# scb_connectors.net
KiCad netlist of a schematic drawn in Altium Designer
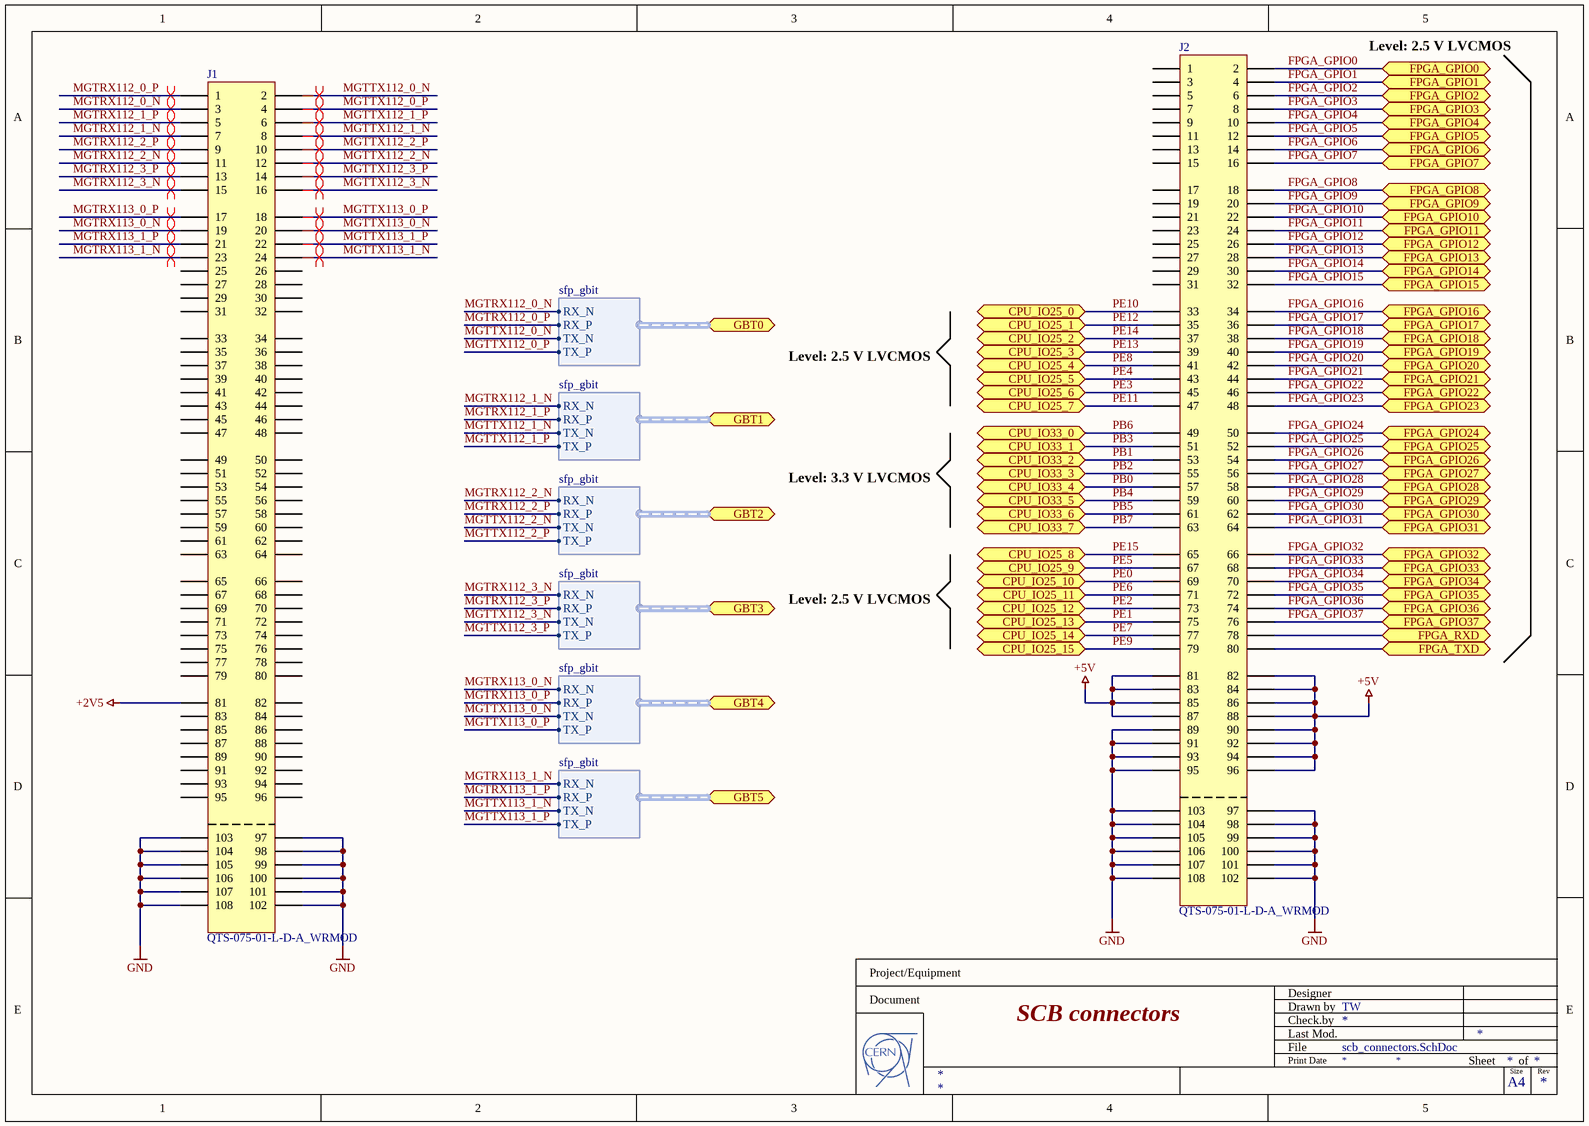
[diagram p0: scb_connectors.SchDoc]

(export (version "E")
  (design (tool "Eeschema 10.0.6"))
  (components
    (comp (ref "J1")
      (value "QTS-075-01-L-D-A_WRMOD")
      (footprint "QTS-075-01-L-D-A_WRMOD")
      (description "High Speed Ground Plane Header")
      (libsource (lib "wr_switch") (part "QTS-075-01-L-D-A_WRMOD"))
    )
    (comp (ref "J2")
      (value "QTS-075-01-L-D-A_WRMOD")
      (footprint "QTS-075-01-L-D-A_WRMOD")
      (description "High Speed Ground Plane Header")
      (libsource (lib "wr_switch") (part "QTS-075-01-L-D-A_WRMOD"))
    )
  )
  (nets
    (net (code "2") (name "+2V5") (class "Default")
      (node (ref "J1") (pin "81") (pinfunction "81_81") (pintype "passive"))
    )
    (net (code "3") (name "+5V") (class "Default")
      (node (ref "J2") (pin "81") (pinfunction "81_81") (pintype "passive"))
      (node (ref "J2") (pin "82") (pinfunction "82_82") (pintype "passive"))
      (node (ref "J2") (pin "83") (pinfunction "83_83") (pintype "passive"))
      (node (ref "J2") (pin "84") (pinfunction "84_84") (pintype "passive"))
      (node (ref "J2") (pin "85") (pinfunction "85_85") (pintype "passive"))
      (node (ref "J2") (pin "86") (pinfunction "86_86") (pintype "passive"))
      (node (ref "J2") (pin "87") (pinfunction "87_87") (pintype "passive"))
      (node (ref "J2") (pin "88") (pinfunction "88_88") (pintype "passive"))
      (node (ref "J2") (pin "90") (pinfunction "90_90") (pintype "passive"))
      (node (ref "J2") (pin "92") (pinfunction "92_92") (pintype "passive"))
      (node (ref "J2") (pin "94") (pinfunction "94_94") (pintype "passive"))
      (node (ref "J2") (pin "96") (pinfunction "96_96") (pintype "passive"))
    )
    (net (code "4") (name "/FPGA_GPIO0") (class "Default")
      (node (ref "J2") (pin "2") (pinfunction "2_2") (pintype "passive"))
    )
    (net (code "5") (name "/FPGA_GPIO1") (class "Default")
      (node (ref "J2") (pin "4") (pinfunction "4_4") (pintype "passive"))
    )
    (net (code "6") (name "/FPGA_GPIO2") (class "Default")
      (node (ref "J2") (pin "6") (pinfunction "6_6") (pintype "passive"))
    )
    (net (code "7") (name "/FPGA_GPIO3") (class "Default")
      (node (ref "J2") (pin "8") (pinfunction "8_8") (pintype "passive"))
    )
    (net (code "8") (name "/FPGA_GPIO4") (class "Default")
      (node (ref "J2") (pin "10") (pinfunction "10_10") (pintype "passive"))
    )
    (net (code "9") (name "/FPGA_GPIO5") (class "Default")
      (node (ref "J2") (pin "12") (pinfunction "12_12") (pintype "passive"))
    )
    (net (code "10") (name "/FPGA_GPIO6") (class "Default")
      (node (ref "J2") (pin "14") (pinfunction "14_14") (pintype "passive"))
    )
    (net (code "11") (name "/FPGA_GPIO7") (class "Default")
      (node (ref "J2") (pin "16") (pinfunction "16_16") (pintype "passive"))
    )
    (net (code "12") (name "/FPGA_GPIO8") (class "Default")
      (node (ref "J2") (pin "18") (pinfunction "18_18") (pintype "passive"))
    )
    (net (code "13") (name "/FPGA_GPIO9") (class "Default")
      (node (ref "J2") (pin "20") (pinfunction "20_20") (pintype "passive"))
    )
    (net (code "14") (name "/FPGA_GPIO10") (class "Default")
      (node (ref "J2") (pin "22") (pinfunction "22_22") (pintype "passive"))
    )
    (net (code "15") (name "/FPGA_GPIO11") (class "Default")
      (node (ref "J2") (pin "24") (pinfunction "24_24") (pintype "passive"))
    )
    (net (code "16") (name "/FPGA_GPIO12") (class "Default")
      (node (ref "J2") (pin "26") (pinfunction "26_26") (pintype "passive"))
    )
    (net (code "17") (name "/FPGA_GPIO13") (class "Default")
      (node (ref "J2") (pin "28") (pinfunction "28_28") (pintype "passive"))
    )
    (net (code "18") (name "/FPGA_GPIO14") (class "Default")
      (node (ref "J2") (pin "30") (pinfunction "30_30") (pintype "passive"))
    )
    (net (code "19") (name "/FPGA_GPIO15") (class "Default")
      (node (ref "J2") (pin "32") (pinfunction "32_32") (pintype "passive"))
    )
    (net (code "20") (name "/FPGA_GPIO16") (class "Default")
      (node (ref "J2") (pin "34") (pinfunction "34_34") (pintype "passive"))
    )
    (net (code "21") (name "/FPGA_GPIO17") (class "Default")
      (node (ref "J2") (pin "36") (pinfunction "36_36") (pintype "passive"))
    )
    (net (code "22") (name "/FPGA_GPIO18") (class "Default")
      (node (ref "J2") (pin "38") (pinfunction "38_38") (pintype "passive"))
    )
    (net (code "23") (name "/FPGA_GPIO19") (class "Default")
      (node (ref "J2") (pin "40") (pinfunction "40_40") (pintype "passive"))
    )
    (net (code "24") (name "/FPGA_GPIO20") (class "Default")
      (node (ref "J2") (pin "42") (pinfunction "42_42") (pintype "passive"))
    )
    (net (code "25") (name "/FPGA_GPIO21") (class "Default")
      (node (ref "J2") (pin "44") (pinfunction "44_44") (pintype "passive"))
    )
    (net (code "26") (name "/FPGA_GPIO22") (class "Default")
      (node (ref "J2") (pin "46") (pinfunction "46_46") (pintype "passive"))
    )
    (net (code "27") (name "/FPGA_GPIO23") (class "Default")
      (node (ref "J2") (pin "48") (pinfunction "48_48") (pintype "passive"))
    )
    (net (code "28") (name "/FPGA_GPIO24") (class "Default")
      (node (ref "J2") (pin "50") (pinfunction "50_50") (pintype "passive"))
    )
    (net (code "29") (name "/FPGA_GPIO25") (class "Default")
      (node (ref "J2") (pin "52") (pinfunction "52_52") (pintype "passive"))
    )
    (net (code "30") (name "/FPGA_GPIO26") (class "Default")
      (node (ref "J2") (pin "54") (pinfunction "54_54") (pintype "passive"))
    )
    (net (code "31") (name "/FPGA_GPIO27") (class "Default")
      (node (ref "J2") (pin "56") (pinfunction "56_56") (pintype "passive"))
    )
    (net (code "32") (name "/FPGA_GPIO28") (class "Default")
      (node (ref "J2") (pin "58") (pinfunction "58_58") (pintype "passive"))
    )
    (net (code "33") (name "/FPGA_GPIO29") (class "Default")
      (node (ref "J2") (pin "60") (pinfunction "60_60") (pintype "passive"))
    )
    (net (code "34") (name "/FPGA_GPIO30") (class "Default")
      (node (ref "J2") (pin "62") (pinfunction "62_62") (pintype "passive"))
    )
    (net (code "35") (name "/FPGA_GPIO31") (class "Default")
      (node (ref "J2") (pin "64") (pinfunction "64_64") (pintype "passive"))
    )
    (net (code "36") (name "/FPGA_GPIO32") (class "Default")
      (node (ref "J2") (pin "66") (pinfunction "66_66") (pintype "passive"))
    )
    (net (code "37") (name "/FPGA_GPIO33") (class "Default")
      (node (ref "J2") (pin "68") (pinfunction "68_68") (pintype "passive"))
    )
    (net (code "38") (name "/FPGA_GPIO34") (class "Default")
      (node (ref "J2") (pin "70") (pinfunction "70_70") (pintype "passive"))
    )
    (net (code "39") (name "/FPGA_GPIO35") (class "Default")
      (node (ref "J2") (pin "72") (pinfunction "72_72") (pintype "passive"))
    )
    (net (code "40") (name "/FPGA_GPIO36") (class "Default")
      (node (ref "J2") (pin "74") (pinfunction "74_74") (pintype "passive"))
    )
    (net (code "41") (name "/FPGA_GPIO37") (class "Default")
      (node (ref "J2") (pin "76") (pinfunction "76_76") (pintype "passive"))
    )
    (net (code "42") (name "/FPGA_RXD") (class "Default")
      (node (ref "J2") (pin "78") (pinfunction "78_78") (pintype "passive"))
    )
    (net (code "43") (name "/FPGA_TXD") (class "Default")
      (node (ref "J2") (pin "80") (pinfunction "80_80") (pintype "passive"))
    )
    (net (code "44") (name "/MGTRX112_0_N") (class "Default")
      (node (ref "J1") (pin "3") (pinfunction "3_3") (pintype "passive"))
    )
    (net (code "45") (name "/MGTRX112_0_P") (class "Default")
      (node (ref "J1") (pin "1") (pinfunction "1_1") (pintype "passive"))
    )
    (net (code "46") (name "/MGTRX112_1_N") (class "Default")
      (node (ref "J1") (pin "7") (pinfunction "7_7") (pintype "passive"))
    )
    (net (code "47") (name "/MGTRX112_1_P") (class "Default")
      (node (ref "J1") (pin "5") (pinfunction "5_5") (pintype "passive"))
    )
    (net (code "48") (name "/MGTRX112_2_N") (class "Default")
      (node (ref "J1") (pin "11") (pinfunction "11_11") (pintype "passive"))
    )
    (net (code "49") (name "/MGTRX112_2_P") (class "Default")
      (node (ref "J1") (pin "9") (pinfunction "9_9") (pintype "passive"))
    )
    (net (code "50") (name "/MGTRX112_3_N") (class "Default")
      (node (ref "J1") (pin "15") (pinfunction "15_15") (pintype "passive"))
    )
    (net (code "51") (name "/MGTRX112_3_P") (class "Default")
      (node (ref "J1") (pin "13") (pinfunction "13_13") (pintype "passive"))
    )
    (net (code "52") (name "/MGTRX113_0_N") (class "Default")
      (node (ref "J1") (pin "19") (pinfunction "19_19") (pintype "passive"))
    )
    (net (code "53") (name "/MGTRX113_0_P") (class "Default")
      (node (ref "J1") (pin "17") (pinfunction "17_17") (pintype "passive"))
    )
    (net (code "54") (name "/MGTRX113_1_N") (class "Default")
      (node (ref "J1") (pin "23") (pinfunction "23_23") (pintype "passive"))
    )
    (net (code "55") (name "/MGTRX113_1_P") (class "Default")
      (node (ref "J1") (pin "21") (pinfunction "21_21") (pintype "passive"))
    )
    (net (code "56") (name "/MGTTX112_0_N") (class "Default")
      (node (ref "J1") (pin "2") (pinfunction "2_2") (pintype "passive"))
    )
    (net (code "57") (name "/MGTTX112_0_P") (class "Default")
      (node (ref "J1") (pin "4") (pinfunction "4_4") (pintype "passive"))
    )
    (net (code "58") (name "/MGTTX112_1_N") (class "Default")
      (node (ref "J1") (pin "8") (pinfunction "8_8") (pintype "passive"))
    )
    (net (code "59") (name "/MGTTX112_1_P") (class "Default")
      (node (ref "J1") (pin "6") (pinfunction "6_6") (pintype "passive"))
    )
    (net (code "60") (name "/MGTTX112_2_N") (class "Default")
      (node (ref "J1") (pin "12") (pinfunction "12_12") (pintype "passive"))
    )
    (net (code "61") (name "/MGTTX112_2_P") (class "Default")
      (node (ref "J1") (pin "10") (pinfunction "10_10") (pintype "passive"))
    )
    (net (code "62") (name "/MGTTX112_3_N") (class "Default")
      (node (ref "J1") (pin "16") (pinfunction "16_16") (pintype "passive"))
    )
    (net (code "63") (name "/MGTTX112_3_P") (class "Default")
      (node (ref "J1") (pin "14") (pinfunction "14_14") (pintype "passive"))
    )
    (net (code "64") (name "/MGTTX113_0_N") (class "Default")
      (node (ref "J1") (pin "20") (pinfunction "20_20") (pintype "passive"))
    )
    (net (code "65") (name "/MGTTX113_0_P") (class "Default")
      (node (ref "J1") (pin "18") (pinfunction "18_18") (pintype "passive"))
    )
    (net (code "66") (name "/MGTTX113_1_N") (class "Default")
      (node (ref "J1") (pin "24") (pinfunction "24_24") (pintype "passive"))
    )
    (net (code "67") (name "/MGTTX113_1_P") (class "Default")
      (node (ref "J1") (pin "22") (pinfunction "22_22") (pintype "passive"))
    )
    (net (code "68") (name "/PB0") (class "Default")
      (node (ref "J2") (pin "57") (pinfunction "57_57") (pintype "passive"))
    )
    (net (code "69") (name "/PB1") (class "Default")
      (node (ref "J2") (pin "53") (pinfunction "53_53") (pintype "passive"))
    )
    (net (code "70") (name "/PB2") (class "Default")
      (node (ref "J2") (pin "55") (pinfunction "55_55") (pintype "passive"))
    )
    (net (code "71") (name "/PB3") (class "Default")
      (node (ref "J2") (pin "51") (pinfunction "51_51") (pintype "passive"))
    )
    (net (code "72") (name "/PB4") (class "Default")
      (node (ref "J2") (pin "59") (pinfunction "59_59") (pintype "passive"))
    )
    (net (code "73") (name "/PB5") (class "Default")
      (node (ref "J2") (pin "61") (pinfunction "61_61") (pintype "passive"))
    )
    (net (code "74") (name "/PB6") (class "Default")
      (node (ref "J2") (pin "49") (pinfunction "49_49") (pintype "passive"))
    )
    (net (code "75") (name "/PB7") (class "Default")
      (node (ref "J2") (pin "63") (pinfunction "63_63") (pintype "passive"))
    )
    (net (code "76") (name "/PE0") (class "Default")
      (node (ref "J2") (pin "69") (pinfunction "69_69") (pintype "passive"))
    )
    (net (code "77") (name "/PE1") (class "Default")
      (node (ref "J2") (pin "75") (pinfunction "75_75") (pintype "passive"))
    )
    (net (code "78") (name "/PE2") (class "Default")
      (node (ref "J2") (pin "73") (pinfunction "73_73") (pintype "passive"))
    )
    (net (code "79") (name "/PE3") (class "Default")
      (node (ref "J2") (pin "45") (pinfunction "45_45") (pintype "passive"))
    )
    (net (code "80") (name "/PE4") (class "Default")
      (node (ref "J2") (pin "43") (pinfunction "43_43") (pintype "passive"))
    )
    (net (code "81") (name "/PE5") (class "Default")
      (node (ref "J2") (pin "67") (pinfunction "67_67") (pintype "passive"))
    )
    (net (code "82") (name "/PE6") (class "Default")
      (node (ref "J2") (pin "71") (pinfunction "71_71") (pintype "passive"))
    )
    (net (code "83") (name "/PE7") (class "Default")
      (node (ref "J2") (pin "77") (pinfunction "77_77") (pintype "passive"))
    )
    (net (code "84") (name "/PE8") (class "Default")
      (node (ref "J2") (pin "41") (pinfunction "41_41") (pintype "passive"))
    )
    (net (code "85") (name "/PE9") (class "Default")
      (node (ref "J2") (pin "79") (pinfunction "79_79") (pintype "passive"))
    )
    (net (code "86") (name "/PE10") (class "Default")
      (node (ref "J2") (pin "33") (pinfunction "33_33") (pintype "passive"))
    )
    (net (code "87") (name "/PE11") (class "Default")
      (node (ref "J2") (pin "47") (pinfunction "47_47") (pintype "passive"))
    )
    (net (code "88") (name "/PE12") (class "Default")
      (node (ref "J2") (pin "35") (pinfunction "35_35") (pintype "passive"))
    )
    (net (code "89") (name "/PE13") (class "Default")
      (node (ref "J2") (pin "39") (pinfunction "39_39") (pintype "passive"))
    )
    (net (code "90") (name "/PE14") (class "Default")
      (node (ref "J2") (pin "37") (pinfunction "37_37") (pintype "passive"))
    )
    (net (code "91") (name "/PE15") (class "Default")
      (node (ref "J2") (pin "65") (pinfunction "65_65") (pintype "passive"))
    )
    (net (code "93") (name "GND") (class "Default")
      (node (ref "J1") (pin "100") (pinfunction "100_100") (pintype "passive"))
      (node (ref "J1") (pin "101") (pinfunction "101_101") (pintype "passive"))
      (node (ref "J1") (pin "102") (pinfunction "102_102") (pintype "passive"))
      (node (ref "J1") (pin "103") (pinfunction "103_103") (pintype "passive"))
      (node (ref "J1") (pin "104") (pinfunction "104_104") (pintype "passive"))
      (node (ref "J1") (pin "105") (pinfunction "105_105") (pintype "passive"))
      (node (ref "J1") (pin "106") (pinfunction "106_106") (pintype "passive"))
      (node (ref "J1") (pin "107") (pinfunction "107_107") (pintype "passive"))
      (node (ref "J1") (pin "108") (pinfunction "108_108") (pintype "passive"))
      (node (ref "J1") (pin "97") (pinfunction "97_97") (pintype "passive"))
      (node (ref "J1") (pin "98") (pinfunction "98_98") (pintype "passive"))
      (node (ref "J1") (pin "99") (pinfunction "99_99") (pintype "passive"))
      (node (ref "J2") (pin "100") (pinfunction "100_100") (pintype "passive"))
      (node (ref "J2") (pin "101") (pinfunction "101_101") (pintype "passive"))
      (node (ref "J2") (pin "102") (pinfunction "102_102") (pintype "passive"))
      (node (ref "J2") (pin "103") (pinfunction "103_103") (pintype "passive"))
      (node (ref "J2") (pin "104") (pinfunction "104_104") (pintype "passive"))
      (node (ref "J2") (pin "105") (pinfunction "105_105") (pintype "passive"))
      (node (ref "J2") (pin "106") (pinfunction "106_106") (pintype "passive"))
      (node (ref "J2") (pin "107") (pinfunction "107_107") (pintype "passive"))
      (node (ref "J2") (pin "108") (pinfunction "108_108") (pintype "passive"))
      (node (ref "J2") (pin "89") (pinfunction "89_89") (pintype "passive"))
      (node (ref "J2") (pin "91") (pinfunction "91_91") (pintype "passive"))
      (node (ref "J2") (pin "93") (pinfunction "93_93") (pintype "passive"))
      (node (ref "J2") (pin "95") (pinfunction "95_95") (pintype "passive"))
      (node (ref "J2") (pin "97") (pinfunction "97_97") (pintype "passive"))
      (node (ref "J2") (pin "98") (pinfunction "98_98") (pintype "passive"))
      (node (ref "J2") (pin "99") (pinfunction "99_99") (pintype "passive"))
    )
    (net (code "94") (name "unconnected-(J1-Pad25)") (class "Default")
      (node (ref "J1") (pin "25") (pinfunction "25_25") (pintype "passive"))
    )
    (net (code "95") (name "unconnected-(J1-Pad26)") (class "Default")
      (node (ref "J1") (pin "26") (pinfunction "26_26") (pintype "passive"))
    )
    (net (code "96") (name "unconnected-(J1-Pad27)") (class "Default")
      (node (ref "J1") (pin "27") (pinfunction "27_27") (pintype "passive"))
    )
    (net (code "97") (name "unconnected-(J1-Pad28)") (class "Default")
      (node (ref "J1") (pin "28") (pinfunction "28_28") (pintype "passive"))
    )
    (net (code "98") (name "unconnected-(J1-Pad29)") (class "Default")
      (node (ref "J1") (pin "29") (pinfunction "29_29") (pintype "passive"))
    )
    (net (code "99") (name "unconnected-(J1-Pad30)") (class "Default")
      (node (ref "J1") (pin "30") (pinfunction "30_30") (pintype "passive"))
    )
    (net (code "100") (name "unconnected-(J1-Pad31)") (class "Default")
      (node (ref "J1") (pin "31") (pinfunction "31_31") (pintype "passive"))
    )
    (net (code "101") (name "unconnected-(J1-Pad32)") (class "Default")
      (node (ref "J1") (pin "32") (pinfunction "32_32") (pintype "passive"))
    )
    (net (code "102") (name "unconnected-(J1-Pad33)") (class "Default")
      (node (ref "J1") (pin "33") (pinfunction "33_33") (pintype "passive"))
    )
    (net (code "103") (name "unconnected-(J1-Pad34)") (class "Default")
      (node (ref "J1") (pin "34") (pinfunction "34_34") (pintype "passive"))
    )
    (net (code "104") (name "unconnected-(J1-Pad35)") (class "Default")
      (node (ref "J1") (pin "35") (pinfunction "35_35") (pintype "passive"))
    )
    (net (code "105") (name "unconnected-(J1-Pad36)") (class "Default")
      (node (ref "J1") (pin "36") (pinfunction "36_36") (pintype "passive"))
    )
    (net (code "106") (name "unconnected-(J1-Pad37)") (class "Default")
      (node (ref "J1") (pin "37") (pinfunction "37_37") (pintype "passive"))
    )
    (net (code "107") (name "unconnected-(J1-Pad38)") (class "Default")
      (node (ref "J1") (pin "38") (pinfunction "38_38") (pintype "passive"))
    )
    (net (code "108") (name "unconnected-(J1-Pad39)") (class "Default")
      (node (ref "J1") (pin "39") (pinfunction "39_39") (pintype "passive"))
    )
    (net (code "109") (name "unconnected-(J1-Pad40)") (class "Default")
      (node (ref "J1") (pin "40") (pinfunction "40_40") (pintype "passive"))
    )
    (net (code "110") (name "unconnected-(J1-Pad41)") (class "Default")
      (node (ref "J1") (pin "41") (pinfunction "41_41") (pintype "passive"))
    )
    (net (code "111") (name "unconnected-(J1-Pad42)") (class "Default")
      (node (ref "J1") (pin "42") (pinfunction "42_42") (pintype "passive"))
    )
    (net (code "112") (name "unconnected-(J1-Pad43)") (class "Default")
      (node (ref "J1") (pin "43") (pinfunction "43_43") (pintype "passive"))
    )
    (net (code "113") (name "unconnected-(J1-Pad44)") (class "Default")
      (node (ref "J1") (pin "44") (pinfunction "44_44") (pintype "passive"))
    )
    (net (code "114") (name "unconnected-(J1-Pad45)") (class "Default")
      (node (ref "J1") (pin "45") (pinfunction "45_45") (pintype "passive"))
    )
    (net (code "115") (name "unconnected-(J1-Pad46)") (class "Default")
      (node (ref "J1") (pin "46") (pinfunction "46_46") (pintype "passive"))
    )
    (net (code "116") (name "unconnected-(J1-Pad47)") (class "Default")
      (node (ref "J1") (pin "47") (pinfunction "47_47") (pintype "passive"))
    )
    (net (code "117") (name "unconnected-(J1-Pad48)") (class "Default")
      (node (ref "J1") (pin "48") (pinfunction "48_48") (pintype "passive"))
    )
    (net (code "118") (name "unconnected-(J1-Pad49)") (class "Default")
      (node (ref "J1") (pin "49") (pinfunction "49_49") (pintype "passive"))
    )
    (net (code "119") (name "unconnected-(J1-Pad50)") (class "Default")
      (node (ref "J1") (pin "50") (pinfunction "50_50") (pintype "passive"))
    )
    (net (code "120") (name "unconnected-(J1-Pad51)") (class "Default")
      (node (ref "J1") (pin "51") (pinfunction "51_51") (pintype "passive"))
    )
    (net (code "121") (name "unconnected-(J1-Pad52)") (class "Default")
      (node (ref "J1") (pin "52") (pinfunction "52_52") (pintype "passive"))
    )
    (net (code "122") (name "unconnected-(J1-Pad53)") (class "Default")
      (node (ref "J1") (pin "53") (pinfunction "53_53") (pintype "passive"))
    )
    (net (code "123") (name "unconnected-(J1-Pad54)") (class "Default")
      (node (ref "J1") (pin "54") (pinfunction "54_54") (pintype "passive"))
    )
    (net (code "124") (name "unconnected-(J1-Pad55)") (class "Default")
      (node (ref "J1") (pin "55") (pinfunction "55_55") (pintype "passive"))
    )
    (net (code "125") (name "unconnected-(J1-Pad56)") (class "Default")
      (node (ref "J1") (pin "56") (pinfunction "56_56") (pintype "passive"))
    )
    (net (code "126") (name "unconnected-(J1-Pad57)") (class "Default")
      (node (ref "J1") (pin "57") (pinfunction "57_57") (pintype "passive"))
    )
    (net (code "127") (name "unconnected-(J1-Pad58)") (class "Default")
      (node (ref "J1") (pin "58") (pinfunction "58_58") (pintype "passive"))
    )
    (net (code "128") (name "unconnected-(J1-Pad59)") (class "Default")
      (node (ref "J1") (pin "59") (pinfunction "59_59") (pintype "passive"))
    )
    (net (code "129") (name "unconnected-(J1-Pad60)") (class "Default")
      (node (ref "J1") (pin "60") (pinfunction "60_60") (pintype "passive"))
    )
    (net (code "130") (name "unconnected-(J1-Pad61)") (class "Default")
      (node (ref "J1") (pin "61") (pinfunction "61_61") (pintype "passive"))
    )
    (net (code "131") (name "unconnected-(J1-Pad62)") (class "Default")
      (node (ref "J1") (pin "62") (pinfunction "62_62") (pintype "passive"))
    )
    (net (code "132") (name "unconnected-(J1-Pad63)") (class "Default")
      (node (ref "J1") (pin "63") (pinfunction "63_63") (pintype "passive"))
    )
    (net (code "133") (name "unconnected-(J1-Pad64)") (class "Default")
      (node (ref "J1") (pin "64") (pinfunction "64_64") (pintype "passive"))
    )
    (net (code "134") (name "unconnected-(J1-Pad65)") (class "Default")
      (node (ref "J1") (pin "65") (pinfunction "65_65") (pintype "passive"))
    )
    (net (code "135") (name "unconnected-(J1-Pad66)") (class "Default")
      (node (ref "J1") (pin "66") (pinfunction "66_66") (pintype "passive"))
    )
    (net (code "136") (name "unconnected-(J1-Pad67)") (class "Default")
      (node (ref "J1") (pin "67") (pinfunction "67_67") (pintype "passive"))
    )
    (net (code "137") (name "unconnected-(J1-Pad68)") (class "Default")
      (node (ref "J1") (pin "68") (pinfunction "68_68") (pintype "passive"))
    )
    (net (code "138") (name "unconnected-(J1-Pad69)") (class "Default")
      (node (ref "J1") (pin "69") (pinfunction "69_69") (pintype "passive"))
    )
    (net (code "139") (name "unconnected-(J1-Pad70)") (class "Default")
      (node (ref "J1") (pin "70") (pinfunction "70_70") (pintype "passive"))
    )
    (net (code "140") (name "unconnected-(J1-Pad71)") (class "Default")
      (node (ref "J1") (pin "71") (pinfunction "71_71") (pintype "passive"))
    )
    (net (code "141") (name "unconnected-(J1-Pad72)") (class "Default")
      (node (ref "J1") (pin "72") (pinfunction "72_72") (pintype "passive"))
    )
    (net (code "142") (name "unconnected-(J1-Pad73)") (class "Default")
      (node (ref "J1") (pin "73") (pinfunction "73_73") (pintype "passive"))
    )
    (net (code "143") (name "unconnected-(J1-Pad74)") (class "Default")
      (node (ref "J1") (pin "74") (pinfunction "74_74") (pintype "passive"))
    )
    (net (code "144") (name "unconnected-(J1-Pad75)") (class "Default")
      (node (ref "J1") (pin "75") (pinfunction "75_75") (pintype "passive"))
    )
    (net (code "145") (name "unconnected-(J1-Pad76)") (class "Default")
      (node (ref "J1") (pin "76") (pinfunction "76_76") (pintype "passive"))
    )
    (net (code "146") (name "unconnected-(J1-Pad77)") (class "Default")
      (node (ref "J1") (pin "77") (pinfunction "77_77") (pintype "passive"))
    )
    (net (code "147") (name "unconnected-(J1-Pad78)") (class "Default")
      (node (ref "J1") (pin "78") (pinfunction "78_78") (pintype "passive"))
    )
    (net (code "148") (name "unconnected-(J1-Pad79)") (class "Default")
      (node (ref "J1") (pin "79") (pinfunction "79_79") (pintype "passive"))
    )
    (net (code "149") (name "unconnected-(J1-Pad80)") (class "Default")
      (node (ref "J1") (pin "80") (pinfunction "80_80") (pintype "passive"))
    )
    (net (code "150") (name "unconnected-(J1-Pad82)") (class "Default")
      (node (ref "J1") (pin "82") (pinfunction "82_82") (pintype "passive"))
    )
    (net (code "151") (name "unconnected-(J1-Pad83)") (class "Default")
      (node (ref "J1") (pin "83") (pinfunction "83_83") (pintype "passive"))
    )
    (net (code "152") (name "unconnected-(J1-Pad84)") (class "Default")
      (node (ref "J1") (pin "84") (pinfunction "84_84") (pintype "passive"))
    )
    (net (code "153") (name "unconnected-(J1-Pad85)") (class "Default")
      (node (ref "J1") (pin "85") (pinfunction "85_85") (pintype "passive"))
    )
    (net (code "154") (name "unconnected-(J1-Pad86)") (class "Default")
      (node (ref "J1") (pin "86") (pinfunction "86_86") (pintype "passive"))
    )
    (net (code "155") (name "unconnected-(J1-Pad87)") (class "Default")
      (node (ref "J1") (pin "87") (pinfunction "87_87") (pintype "passive"))
    )
    (net (code "156") (name "unconnected-(J1-Pad88)") (class "Default")
      (node (ref "J1") (pin "88") (pinfunction "88_88") (pintype "passive"))
    )
    (net (code "157") (name "unconnected-(J1-Pad89)") (class "Default")
      (node (ref "J1") (pin "89") (pinfunction "89_89") (pintype "passive"))
    )
    (net (code "158") (name "unconnected-(J1-Pad90)") (class "Default")
      (node (ref "J1") (pin "90") (pinfunction "90_90") (pintype "passive"))
    )
    (net (code "159") (name "unconnected-(J1-Pad91)") (class "Default")
      (node (ref "J1") (pin "91") (pinfunction "91_91") (pintype "passive"))
    )
    (net (code "160") (name "unconnected-(J1-Pad92)") (class "Default")
      (node (ref "J1") (pin "92") (pinfunction "92_92") (pintype "passive"))
    )
    (net (code "161") (name "unconnected-(J1-Pad93)") (class "Default")
      (node (ref "J1") (pin "93") (pinfunction "93_93") (pintype "passive"))
    )
    (net (code "162") (name "unconnected-(J1-Pad94)") (class "Default")
      (node (ref "J1") (pin "94") (pinfunction "94_94") (pintype "passive"))
    )
    (net (code "163") (name "unconnected-(J1-Pad95)") (class "Default")
      (node (ref "J1") (pin "95") (pinfunction "95_95") (pintype "passive"))
    )
    (net (code "164") (name "unconnected-(J1-Pad96)") (class "Default")
      (node (ref "J1") (pin "96") (pinfunction "96_96") (pintype "passive"))
    )
    (net (code "165") (name "unconnected-(J2-Pad1)") (class "Default")
      (node (ref "J2") (pin "1") (pinfunction "1_1") (pintype "passive"))
    )
    (net (code "166") (name "unconnected-(J2-Pad3)") (class "Default")
      (node (ref "J2") (pin "3") (pinfunction "3_3") (pintype "passive"))
    )
    (net (code "167") (name "unconnected-(J2-Pad5)") (class "Default")
      (node (ref "J2") (pin "5") (pinfunction "5_5") (pintype "passive"))
    )
    (net (code "168") (name "unconnected-(J2-Pad7)") (class "Default")
      (node (ref "J2") (pin "7") (pinfunction "7_7") (pintype "passive"))
    )
    (net (code "169") (name "unconnected-(J2-Pad9)") (class "Default")
      (node (ref "J2") (pin "9") (pinfunction "9_9") (pintype "passive"))
    )
    (net (code "170") (name "unconnected-(J2-Pad11)") (class "Default")
      (node (ref "J2") (pin "11") (pinfunction "11_11") (pintype "passive"))
    )
    (net (code "171") (name "unconnected-(J2-Pad13)") (class "Default")
      (node (ref "J2") (pin "13") (pinfunction "13_13") (pintype "passive"))
    )
    (net (code "172") (name "unconnected-(J2-Pad15)") (class "Default")
      (node (ref "J2") (pin "15") (pinfunction "15_15") (pintype "passive"))
    )
    (net (code "173") (name "unconnected-(J2-Pad17)") (class "Default")
      (node (ref "J2") (pin "17") (pinfunction "17_17") (pintype "passive"))
    )
    (net (code "174") (name "unconnected-(J2-Pad19)") (class "Default")
      (node (ref "J2") (pin "19") (pinfunction "19_19") (pintype "passive"))
    )
    (net (code "175") (name "unconnected-(J2-Pad21)") (class "Default")
      (node (ref "J2") (pin "21") (pinfunction "21_21") (pintype "passive"))
    )
    (net (code "176") (name "unconnected-(J2-Pad23)") (class "Default")
      (node (ref "J2") (pin "23") (pinfunction "23_23") (pintype "passive"))
    )
    (net (code "177") (name "unconnected-(J2-Pad25)") (class "Default")
      (node (ref "J2") (pin "25") (pinfunction "25_25") (pintype "passive"))
    )
    (net (code "178") (name "unconnected-(J2-Pad27)") (class "Default")
      (node (ref "J2") (pin "27") (pinfunction "27_27") (pintype "passive"))
    )
    (net (code "179") (name "unconnected-(J2-Pad29)") (class "Default")
      (node (ref "J2") (pin "29") (pinfunction "29_29") (pintype "passive"))
    )
    (net (code "180") (name "unconnected-(J2-Pad31)") (class "Default")
      (node (ref "J2") (pin "31") (pinfunction "31_31") (pintype "passive"))
    )
  )
)
